# pcb_telemetria_caqui.net
KiCad netlist of a schematic drawn in EAGLE
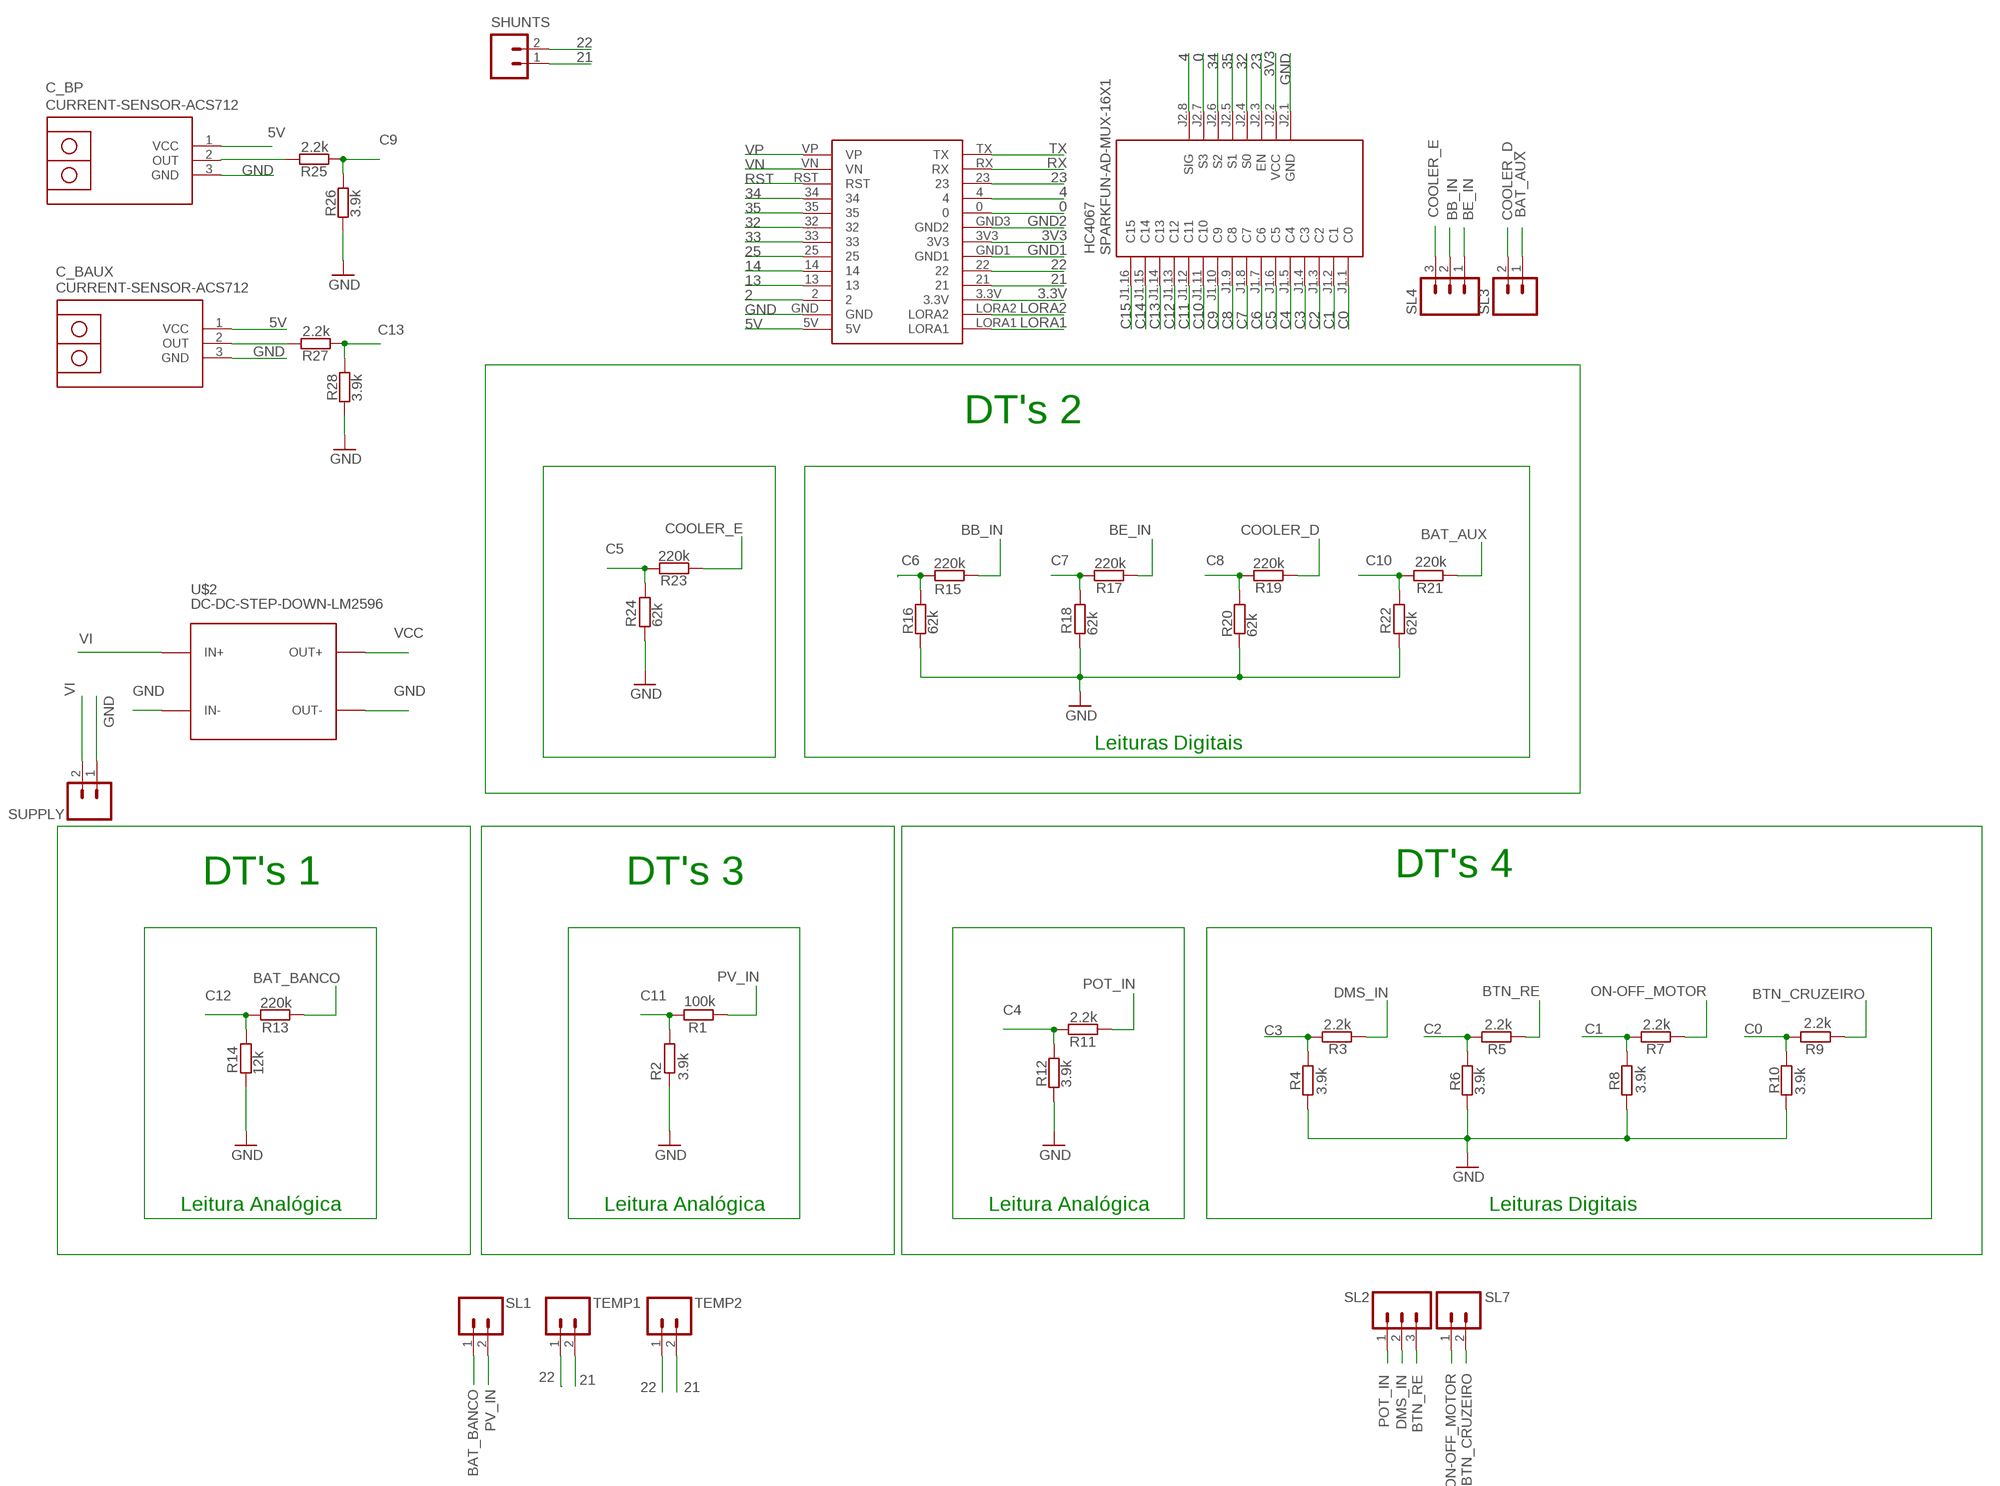
[diagram p0: schematic, sheet 1]

(export (version "E")
  (design (tool "Eeschema 10.0.6"))
  (components
    (comp (ref "C_BAUX")
      (value "CURRENT-SENSOR-ACS712")
      (footprint "eagle-import:CURRENT-SENSOR-ACS712")
      (libsource (lib "eagle-import") (part "CURRENT-SENSOR-ACS712"))
    )
    (comp (ref "C_BP")
      (value "CURRENT-SENSOR-ACS712")
      (footprint "eagle-import:CURRENT-SENSOR-ACS712")
      (libsource (lib "eagle-import") (part "CURRENT-SENSOR-ACS712"))
    )
    (comp (ref "HC4067")
      (value "SPARKFUN-AD-MUX-16X1")
      (footprint "eagle-import:SPARKFUN-AD-MUX-16X1")
      (libsource (lib "eagle-import") (part "SPARKFUN-AD-MUX-16X1"))
    )
    (comp (ref "R1")
      (value "100k")
      (footprint "eagle-import:0204_7")
      (libsource (lib "eagle-import") (part "R-EU_0204/7"))
    )
    (comp (ref "R2")
      (value "3.9k")
      (footprint "eagle-import:0204_7")
      (libsource (lib "eagle-import") (part "R-EU_0204/7"))
    )
    (comp (ref "R3")
      (value "2.2k")
      (footprint "eagle-import:0204_7")
      (libsource (lib "eagle-import") (part "R-EU_0204/7"))
    )
    (comp (ref "R4")
      (value "3.9k")
      (footprint "eagle-import:0204_7")
      (libsource (lib "eagle-import") (part "R-EU_0204/7"))
    )
    (comp (ref "R5")
      (value "2.2k")
      (footprint "eagle-import:0204_7")
      (libsource (lib "eagle-import") (part "R-EU_0204/7"))
    )
    (comp (ref "R6")
      (value "3.9k")
      (footprint "eagle-import:0204_7")
      (libsource (lib "eagle-import") (part "R-EU_0204/7"))
    )
    (comp (ref "R7")
      (value "2.2k")
      (footprint "eagle-import:0204_7")
      (libsource (lib "eagle-import") (part "R-EU_0204/7"))
    )
    (comp (ref "R8")
      (value "3.9k")
      (footprint "eagle-import:0204_7")
      (libsource (lib "eagle-import") (part "R-EU_0204/7"))
    )
    (comp (ref "R9")
      (value "2.2k")
      (footprint "eagle-import:0204_7")
      (libsource (lib "eagle-import") (part "R-EU_0204/7"))
    )
    (comp (ref "R10")
      (value "3.9k")
      (footprint "eagle-import:0204_7")
      (libsource (lib "eagle-import") (part "R-EU_0204/7"))
    )
    (comp (ref "R11")
      (value "2.2k")
      (footprint "eagle-import:0204_7")
      (libsource (lib "eagle-import") (part "R-EU_0204/7"))
    )
    (comp (ref "R12")
      (value "3.9k")
      (footprint "eagle-import:0204_7")
      (libsource (lib "eagle-import") (part "R-EU_0204/7"))
    )
    (comp (ref "R13")
      (value "220k")
      (footprint "eagle-import:0204_7")
      (libsource (lib "eagle-import") (part "R-EU_0204/7"))
    )
    (comp (ref "R14")
      (value "12k")
      (footprint "eagle-import:0204_7")
      (libsource (lib "eagle-import") (part "R-EU_0204/7"))
    )
    (comp (ref "R15")
      (value "220k")
      (footprint "eagle-import:0204_7")
      (libsource (lib "eagle-import") (part "R-EU_0204/7"))
    )
    (comp (ref "R16")
      (value "62k")
      (footprint "eagle-import:0204_7")
      (libsource (lib "eagle-import") (part "R-EU_0204/7"))
    )
    (comp (ref "R17")
      (value "220k")
      (footprint "eagle-import:0204_7")
      (libsource (lib "eagle-import") (part "R-EU_0204/7"))
    )
    (comp (ref "R18")
      (value "62k")
      (footprint "eagle-import:0204_7")
      (libsource (lib "eagle-import") (part "R-EU_0204/7"))
    )
    (comp (ref "R19")
      (value "220k")
      (footprint "eagle-import:0204_7")
      (libsource (lib "eagle-import") (part "R-EU_0204/7"))
    )
    (comp (ref "R20")
      (value "62k")
      (footprint "eagle-import:0204_7")
      (libsource (lib "eagle-import") (part "R-EU_0204/7"))
    )
    (comp (ref "R21")
      (value "220k")
      (footprint "eagle-import:0204_7")
      (libsource (lib "eagle-import") (part "R-EU_0204/7"))
    )
    (comp (ref "R22")
      (value "62k")
      (footprint "eagle-import:0204_7")
      (libsource (lib "eagle-import") (part "R-EU_0204/7"))
    )
    (comp (ref "R23")
      (value "220k")
      (footprint "eagle-import:0204_7")
      (libsource (lib "eagle-import") (part "R-EU_0204/7"))
    )
    (comp (ref "R24")
      (value "62k")
      (footprint "eagle-import:0204_7")
      (libsource (lib "eagle-import") (part "R-EU_0204/7"))
    )
    (comp (ref "R25")
      (value "2.2k")
      (footprint "eagle-import:0204_7")
      (libsource (lib "eagle-import") (part "R-EU_0204/7"))
    )
    (comp (ref "R26")
      (value "3.9k")
      (footprint "eagle-import:0204_7")
      (libsource (lib "eagle-import") (part "R-EU_0204/7"))
    )
    (comp (ref "R27")
      (value "2.2k")
      (footprint "eagle-import:0204_7")
      (libsource (lib "eagle-import") (part "R-EU_0204/7"))
    )
    (comp (ref "R28")
      (value "3.9k")
      (footprint "eagle-import:0204_7")
      (libsource (lib "eagle-import") (part "R-EU_0204/7"))
    )
    (comp (ref "SHUNTS")
      (value "M02")
      (footprint "eagle-import:02P")
      (libsource (lib "eagle-import") (part "M02"))
    )
    (comp (ref "SL1")
      (value "M02")
      (footprint "eagle-import:02P")
      (libsource (lib "eagle-import") (part "M02"))
    )
    (comp (ref "SL2")
      (value "M03")
      (footprint "eagle-import:03P")
      (libsource (lib "eagle-import") (part "M03"))
    )
    (comp (ref "SL3")
      (value "M02")
      (footprint "eagle-import:02P")
      (libsource (lib "eagle-import") (part "M02"))
    )
    (comp (ref "SL4")
      (value "M03")
      (footprint "eagle-import:03P")
      (libsource (lib "eagle-import") (part "M03"))
    )
    (comp (ref "SL7")
      (value "M02")
      (footprint "eagle-import:02P")
      (libsource (lib "eagle-import") (part "M02"))
    )
    (comp (ref "SUPPLY")
      (value "M02")
      (footprint "eagle-import:02P")
      (libsource (lib "eagle-import") (part "M02"))
    )
    (comp (ref "TEMP1")
      (value "M02")
      (footprint "eagle-import:02P")
      (libsource (lib "eagle-import") (part "M02"))
    )
    (comp (ref "TEMP2")
      (value "M02")
      (footprint "eagle-import:02P")
      (libsource (lib "eagle-import") (part "M02"))
    )
    (comp (ref "U$1")
      (value "TTGOBEAM")
      (footprint "eagle-import:TTGOBEAM")
      (libsource (lib "eagle-import") (part "TTGOBEAM"))
    )
    (comp (ref "U$2")
      (value "DC-DC-STEP-DOWN-LM2596")
      (footprint "eagle-import:DC-DC-STEP-DOWN-LM2596")
      (libsource (lib "eagle-import") (part "DC-DC-STEP-DOWN-LM2596"))
    )
  )
  (nets
    (net (code "1") (name "/0") (class "Default")
      (node (ref "HC4067") (pin "J2.7") (pinfunction "S3_J2.7") (pintype "bidirectional"))
      (node (ref "U$1") (pin "0") (pinfunction "0_0") (pintype "bidirectional"))
    )
    (net (code "2") (name "/2") (class "Default")
      (node (ref "U$1") (pin "2") (pinfunction "2_2") (pintype "bidirectional"))
    )
    (net (code "3") (name "/3.3V") (class "Default")
      (node (ref "U$1") (pin "3.3V") (pinfunction "3.3V_3.3V") (pintype "bidirectional"))
    )
    (net (code "4") (name "/3V3") (class "Default")
      (node (ref "HC4067") (pin "J2.2") (pinfunction "VCC_J2.2") (pintype "power_in"))
      (node (ref "U$1") (pin "3V3") (pinfunction "3V3_3V3") (pintype "bidirectional"))
    )
    (net (code "5") (name "/4") (class "Default")
      (node (ref "HC4067") (pin "J2.8") (pinfunction "SIG_J2.8") (pintype "bidirectional"))
      (node (ref "U$1") (pin "4") (pinfunction "4_4") (pintype "bidirectional"))
    )
    (net (code "6") (name "/5V") (class "Default")
      (node (ref "C_BAUX") (pin "1") (pinfunction "VCC_1") (pintype "power_in"))
      (node (ref "C_BP") (pin "1") (pinfunction "VCC_1") (pintype "power_in"))
      (node (ref "U$1") (pin "5V") (pinfunction "5V_5V") (pintype "bidirectional"))
    )
    (net (code "7") (name "/13") (class "Default")
      (node (ref "U$1") (pin "13") (pinfunction "13_13") (pintype "bidirectional"))
    )
    (net (code "8") (name "/14") (class "Default")
      (node (ref "U$1") (pin "14") (pinfunction "14_14") (pintype "bidirectional"))
    )
    (net (code "9") (name "/21") (class "Default")
      (node (ref "SHUNTS") (pin "1") (pinfunction "1_1") (pintype "passive"))
      (node (ref "TEMP1") (pin "2") (pinfunction "2_2") (pintype "passive"))
      (node (ref "TEMP2") (pin "2") (pinfunction "2_2") (pintype "passive"))
      (node (ref "U$1") (pin "21") (pinfunction "21_21") (pintype "bidirectional"))
    )
    (net (code "10") (name "/22") (class "Default")
      (node (ref "SHUNTS") (pin "2") (pinfunction "2_2") (pintype "passive"))
      (node (ref "TEMP1") (pin "1") (pinfunction "1_1") (pintype "passive"))
      (node (ref "TEMP2") (pin "1") (pinfunction "1_1") (pintype "passive"))
      (node (ref "U$1") (pin "22") (pinfunction "22_22") (pintype "bidirectional"))
    )
    (net (code "11") (name "/23") (class "Default")
      (node (ref "HC4067") (pin "J2.3") (pinfunction "EN_J2.3") (pintype "input"))
      (node (ref "U$1") (pin "23") (pinfunction "23_23") (pintype "bidirectional"))
    )
    (net (code "12") (name "/25") (class "Default")
      (node (ref "U$1") (pin "25") (pinfunction "25_25") (pintype "bidirectional"))
    )
    (net (code "13") (name "/32") (class "Default")
      (node (ref "HC4067") (pin "J2.4") (pinfunction "S0_J2.4") (pintype "bidirectional"))
      (node (ref "U$1") (pin "32") (pinfunction "32_32") (pintype "bidirectional"))
    )
    (net (code "14") (name "/33") (class "Default")
      (node (ref "U$1") (pin "33") (pinfunction "33_33") (pintype "bidirectional"))
    )
    (net (code "15") (name "/34") (class "Default")
      (node (ref "HC4067") (pin "J2.6") (pinfunction "S2_J2.6") (pintype "bidirectional"))
      (node (ref "U$1") (pin "34") (pinfunction "34_34") (pintype "bidirectional"))
    )
    (net (code "16") (name "/35") (class "Default")
      (node (ref "HC4067") (pin "J2.5") (pinfunction "S1_J2.5") (pintype "bidirectional"))
      (node (ref "U$1") (pin "35") (pinfunction "35_35") (pintype "bidirectional"))
    )
    (net (code "17") (name "/BAT_AUX") (class "Default")
      (node (ref "R21") (pin "2") (pinfunction "2_2") (pintype "passive"))
      (node (ref "SL3") (pin "1") (pinfunction "1_1") (pintype "passive"))
    )
    (net (code "18") (name "/BAT_BANCO") (class "Default")
      (node (ref "R13") (pin "2") (pinfunction "2_2") (pintype "passive"))
      (node (ref "SL1") (pin "1") (pinfunction "1_1") (pintype "passive"))
    )
    (net (code "19") (name "/BB_IN") (class "Default")
      (node (ref "R15") (pin "1") (pinfunction "1_1") (pintype "passive"))
      (node (ref "SL4") (pin "2") (pinfunction "2_2") (pintype "passive"))
    )
    (net (code "20") (name "/BE_IN") (class "Default")
      (node (ref "R17") (pin "2") (pinfunction "2_2") (pintype "passive"))
      (node (ref "SL4") (pin "1") (pinfunction "1_1") (pintype "passive"))
    )
    (net (code "21") (name "/BTN_CRUZEIRO") (class "Default")
      (node (ref "R9") (pin "2") (pinfunction "2_2") (pintype "passive"))
      (node (ref "SL7") (pin "2") (pinfunction "2_2") (pintype "passive"))
    )
    (net (code "22") (name "/BTN_RE") (class "Default")
      (node (ref "R5") (pin "2") (pinfunction "2_2") (pintype "passive"))
      (node (ref "SL2") (pin "3") (pinfunction "3_3") (pintype "passive"))
    )
    (net (code "23") (name "/C0") (class "Default")
      (node (ref "HC4067") (pin "J1.1") (pinfunction "C0_J1.1") (pintype "bidirectional"))
      (node (ref "R10") (pin "2") (pinfunction "2_2") (pintype "passive"))
      (node (ref "R9") (pin "1") (pinfunction "1_1") (pintype "passive"))
    )
    (net (code "24") (name "/C1") (class "Default")
      (node (ref "HC4067") (pin "J1.2") (pinfunction "C1_J1.2") (pintype "bidirectional"))
      (node (ref "R7") (pin "2") (pinfunction "2_2") (pintype "passive"))
      (node (ref "R8") (pin "1") (pinfunction "1_1") (pintype "passive"))
    )
    (net (code "25") (name "/C2") (class "Default")
      (node (ref "HC4067") (pin "J1.3") (pinfunction "C2_J1.3") (pintype "bidirectional"))
      (node (ref "R5") (pin "1") (pinfunction "1_1") (pintype "passive"))
      (node (ref "R6") (pin "2") (pinfunction "2_2") (pintype "passive"))
    )
    (net (code "26") (name "/C3") (class "Default")
      (node (ref "HC4067") (pin "J1.4") (pinfunction "C3_J1.4") (pintype "bidirectional"))
      (node (ref "R3") (pin "2") (pinfunction "2_2") (pintype "passive"))
      (node (ref "R4") (pin "1") (pinfunction "1_1") (pintype "passive"))
    )
    (net (code "27") (name "/C4") (class "Default")
      (node (ref "HC4067") (pin "J1.5") (pinfunction "C4_J1.5") (pintype "bidirectional"))
      (node (ref "R11") (pin "2") (pinfunction "2_2") (pintype "passive"))
      (node (ref "R12") (pin "1") (pinfunction "1_1") (pintype "passive"))
    )
    (net (code "28") (name "/C5") (class "Default")
      (node (ref "HC4067") (pin "J1.6") (pinfunction "C5_J1.6") (pintype "bidirectional"))
      (node (ref "R23") (pin "2") (pinfunction "2_2") (pintype "passive"))
      (node (ref "R24") (pin "1") (pinfunction "1_1") (pintype "passive"))
    )
    (net (code "29") (name "/C6") (class "Default")
      (node (ref "HC4067") (pin "J1.7") (pinfunction "C6_J1.7") (pintype "bidirectional"))
      (node (ref "R15") (pin "2") (pinfunction "2_2") (pintype "passive"))
      (node (ref "R16") (pin "1") (pinfunction "1_1") (pintype "passive"))
    )
    (net (code "30") (name "/C7") (class "Default")
      (node (ref "HC4067") (pin "J1.8") (pinfunction "C7_J1.8") (pintype "bidirectional"))
      (node (ref "R17") (pin "1") (pinfunction "1_1") (pintype "passive"))
      (node (ref "R18") (pin "2") (pinfunction "2_2") (pintype "passive"))
    )
    (net (code "31") (name "/C8") (class "Default")
      (node (ref "HC4067") (pin "J1.9") (pinfunction "C8_J1.9") (pintype "bidirectional"))
      (node (ref "R19") (pin "2") (pinfunction "2_2") (pintype "passive"))
      (node (ref "R20") (pin "1") (pinfunction "1_1") (pintype "passive"))
    )
    (net (code "32") (name "/C9") (class "Default")
      (node (ref "HC4067") (pin "J1.10") (pinfunction "C9_J1.10") (pintype "bidirectional"))
      (node (ref "R25") (pin "1") (pinfunction "1_1") (pintype "passive"))
      (node (ref "R26") (pin "1") (pinfunction "1_1") (pintype "passive"))
    )
    (net (code "33") (name "/C10") (class "Default")
      (node (ref "HC4067") (pin "J1.11") (pinfunction "C10_J1.11") (pintype "bidirectional"))
      (node (ref "R21") (pin "1") (pinfunction "1_1") (pintype "passive"))
      (node (ref "R22") (pin "2") (pinfunction "2_2") (pintype "passive"))
    )
    (net (code "34") (name "/C11") (class "Default")
      (node (ref "HC4067") (pin "J1.12") (pinfunction "C11_J1.12") (pintype "bidirectional"))
      (node (ref "R1") (pin "1") (pinfunction "1_1") (pintype "passive"))
      (node (ref "R2") (pin "2") (pinfunction "2_2") (pintype "passive"))
    )
    (net (code "35") (name "/C12") (class "Default")
      (node (ref "HC4067") (pin "J1.13") (pinfunction "C12_J1.13") (pintype "bidirectional"))
      (node (ref "R13") (pin "1") (pinfunction "1_1") (pintype "passive"))
      (node (ref "R14") (pin "2") (pinfunction "2_2") (pintype "passive"))
    )
    (net (code "36") (name "/C13") (class "Default")
      (node (ref "HC4067") (pin "J1.14") (pinfunction "C13_J1.14") (pintype "bidirectional"))
      (node (ref "R27") (pin "1") (pinfunction "1_1") (pintype "passive"))
      (node (ref "R28") (pin "1") (pinfunction "1_1") (pintype "passive"))
    )
    (net (code "37") (name "/C14") (class "Default")
      (node (ref "HC4067") (pin "J1.15") (pinfunction "C14_J1.15") (pintype "bidirectional"))
    )
    (net (code "38") (name "/C15") (class "Default")
      (node (ref "HC4067") (pin "J1.16") (pinfunction "C15_J1.16") (pintype "bidirectional"))
    )
    (net (code "39") (name "/COOLER_D") (class "Default")
      (node (ref "R19") (pin "1") (pinfunction "1_1") (pintype "passive"))
      (node (ref "SL3") (pin "2") (pinfunction "2_2") (pintype "passive"))
    )
    (net (code "40") (name "/COOLER_E") (class "Default")
      (node (ref "R23") (pin "1") (pinfunction "1_1") (pintype "passive"))
      (node (ref "SL4") (pin "3") (pinfunction "3_3") (pintype "passive"))
    )
    (net (code "41") (name "/DMS_IN") (class "Default")
      (node (ref "R3") (pin "1") (pinfunction "1_1") (pintype "passive"))
      (node (ref "SL2") (pin "2") (pinfunction "2_2") (pintype "passive"))
    )
    (net (code "42") (name "/GND1") (class "Default")
      (node (ref "U$1") (pin "GND1") (pinfunction "GND1_GND1") (pintype "bidirectional"))
    )
    (net (code "43") (name "/GND2") (class "Default")
      (node (ref "U$1") (pin "GND3") (pinfunction "GND2_GND3") (pintype "bidirectional"))
    )
    (net (code "44") (name "/LORA1") (class "Default")
      (node (ref "U$1") (pin "LORA1") (pinfunction "LORA1_LORA1") (pintype "bidirectional"))
    )
    (net (code "45") (name "/LORA2") (class "Default")
      (node (ref "U$1") (pin "LORA2") (pinfunction "LORA2_LORA2") (pintype "bidirectional"))
    )
    (net (code "46") (name "/ON-OFF_MOTOR") (class "Default")
      (node (ref "R7") (pin "1") (pinfunction "1_1") (pintype "passive"))
      (node (ref "SL7") (pin "1") (pinfunction "1_1") (pintype "passive"))
    )
    (net (code "47") (name "/POT_IN") (class "Default")
      (node (ref "R11") (pin "1") (pinfunction "1_1") (pintype "passive"))
      (node (ref "SL2") (pin "1") (pinfunction "1_1") (pintype "passive"))
    )
    (net (code "48") (name "/PV_IN") (class "Default")
      (node (ref "R1") (pin "2") (pinfunction "2_2") (pintype "passive"))
      (node (ref "SL1") (pin "2") (pinfunction "2_2") (pintype "passive"))
    )
    (net (code "49") (name "/RST") (class "Default")
      (node (ref "U$1") (pin "RST") (pinfunction "RST_RST") (pintype "bidirectional"))
    )
    (net (code "50") (name "/RX") (class "Default")
      (node (ref "U$1") (pin "RX") (pinfunction "RX_RX") (pintype "bidirectional"))
    )
    (net (code "51") (name "/TX") (class "Default")
      (node (ref "U$1") (pin "TX") (pinfunction "TX_TX") (pintype "bidirectional"))
    )
    (net (code "52") (name "/VCC") (class "Default")
      (node (ref "U$2") (pin "OUT+") (pinfunction "OUT+_OUT+") (pintype "bidirectional"))
    )
    (net (code "53") (name "/VI") (class "Default")
      (node (ref "SUPPLY") (pin "2") (pinfunction "2_2") (pintype "passive"))
      (node (ref "U$2") (pin "IN+") (pinfunction "IN+_IN+") (pintype "bidirectional"))
    )
    (net (code "54") (name "/VN") (class "Default")
      (node (ref "U$1") (pin "VN") (pinfunction "VN_VN") (pintype "bidirectional"))
    )
    (net (code "55") (name "/VP") (class "Default")
      (node (ref "U$1") (pin "VP") (pinfunction "VP_VP") (pintype "bidirectional"))
    )
    (net (code "56") (name "GND") (class "Default")
      (node (ref "C_BAUX") (pin "3") (pinfunction "GND_3") (pintype "power_in"))
      (node (ref "C_BP") (pin "3") (pinfunction "GND_3") (pintype "power_in"))
      (node (ref "HC4067") (pin "J2.1") (pinfunction "GND_J2.1") (pintype "power_in"))
      (node (ref "R10") (pin "1") (pinfunction "1_1") (pintype "passive"))
      (node (ref "R12") (pin "2") (pinfunction "2_2") (pintype "passive"))
      (node (ref "R14") (pin "1") (pinfunction "1_1") (pintype "passive"))
      (node (ref "R16") (pin "2") (pinfunction "2_2") (pintype "passive"))
      (node (ref "R18") (pin "1") (pinfunction "1_1") (pintype "passive"))
      (node (ref "R2") (pin "1") (pinfunction "1_1") (pintype "passive"))
      (node (ref "R20") (pin "2") (pinfunction "2_2") (pintype "passive"))
      (node (ref "R22") (pin "1") (pinfunction "1_1") (pintype "passive"))
      (node (ref "R24") (pin "2") (pinfunction "2_2") (pintype "passive"))
      (node (ref "R26") (pin "2") (pinfunction "2_2") (pintype "passive"))
      (node (ref "R28") (pin "2") (pinfunction "2_2") (pintype "passive"))
      (node (ref "R4") (pin "2") (pinfunction "2_2") (pintype "passive"))
      (node (ref "R6") (pin "1") (pinfunction "1_1") (pintype "passive"))
      (node (ref "R8") (pin "2") (pinfunction "2_2") (pintype "passive"))
      (node (ref "SUPPLY") (pin "1") (pinfunction "1_1") (pintype "passive"))
      (node (ref "U$1") (pin "GND") (pinfunction "GND_GND") (pintype "bidirectional"))
      (node (ref "U$2") (pin "IN-") (pinfunction "IN-_IN-") (pintype "bidirectional"))
      (node (ref "U$2") (pin "OUT-") (pinfunction "OUT-_OUT-") (pintype "bidirectional"))
    )
    (net (code "57") (name "Net-(C_BAUX-OUT)") (class "Default")
      (node (ref "C_BAUX") (pin "2") (pinfunction "OUT_2") (pintype "output"))
      (node (ref "R27") (pin "2") (pinfunction "2_2") (pintype "passive"))
    )
    (net (code "58") (name "Net-(C_BP-OUT)") (class "Default")
      (node (ref "C_BP") (pin "2") (pinfunction "OUT_2") (pintype "output"))
      (node (ref "R25") (pin "2") (pinfunction "2_2") (pintype "passive"))
    )
  )
)
